# MidiInterface.net
KiCad netlist of a schematic drawn in EAGLE
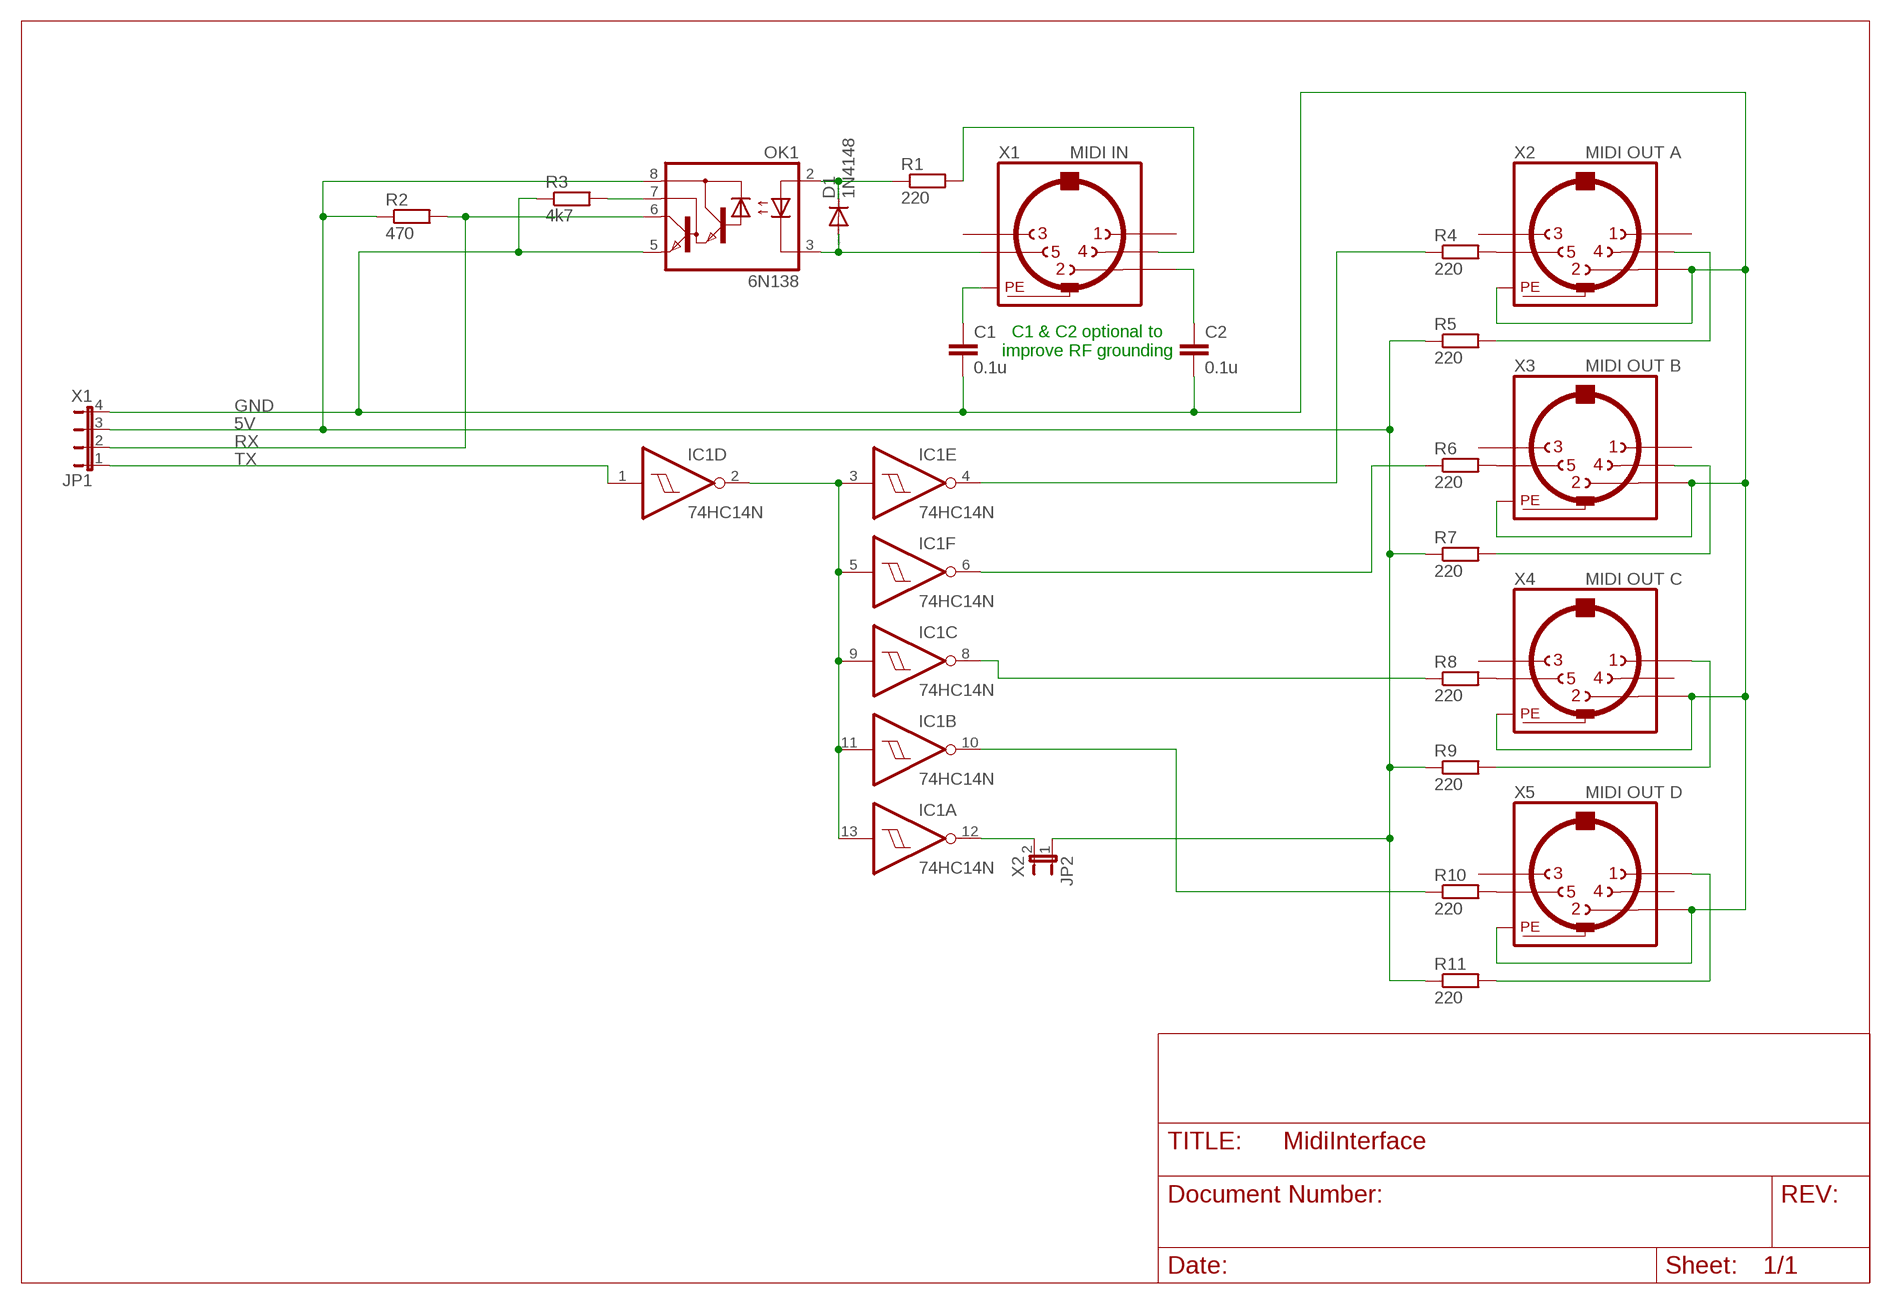
[diagram p0: schematic, sheet 1]

(export (version "E")
  (design (tool "Eeschema 10.0.6"))
  (components
    (comp (ref "C1")
      (value "0.1u")
      (footprint "eagle-import:C025-025X050")
      (libsource (lib "eagle-import") (part "C-EU025-025X050"))
    )
    (comp (ref "C2")
      (value "0.1u")
      (footprint "eagle-import:C025-025X050")
      (libsource (lib "eagle-import") (part "C-EU025-025X050"))
    )
    (comp (ref "D1")
      (value "1N4148")
      (footprint "eagle-import:DO35-7")
      (libsource (lib "eagle-import") (part "1N4148DO35-7"))
    )
    (comp (ref "IC1")
      (value "74HC14N")
      (footprint "eagle-import:DIL14")
      (libsource (lib "eagle-import") (part "7414NHC"))
    )
    (comp (ref "JP1")
      (value "X1")
      (footprint "eagle-import:JP4")
      (libsource (lib "eagle-import") (part "JP4E"))
    )
    (comp (ref "JP2")
      (value "X2")
      (footprint "eagle-import:JP1")
      (libsource (lib "eagle-import") (part "JP1E"))
    )
    (comp (ref "OK1")
      (value "6N138")
      (footprint "eagle-import:DIL08")
      (fields (field (name "MF") "VISHAY/TELEFUNKEN"))
      (libsource (lib "eagle-import") (part "6N138"))
    )
    (comp (ref "R1")
      (value "220")
      (footprint "eagle-import:0204_7")
      (libsource (lib "eagle-import") (part "R-EU_0204/7"))
    )
    (comp (ref "R2")
      (value "470")
      (footprint "eagle-import:0204_7")
      (libsource (lib "eagle-import") (part "R-EU_0204/7"))
    )
    (comp (ref "R3")
      (value "4k7")
      (footprint "eagle-import:0204_7")
      (libsource (lib "eagle-import") (part "R-EU_0204/7"))
    )
    (comp (ref "R4")
      (value "220")
      (footprint "eagle-import:0204_7")
      (libsource (lib "eagle-import") (part "R-EU_0204/7"))
    )
    (comp (ref "R5")
      (value "220")
      (footprint "eagle-import:0204_7")
      (libsource (lib "eagle-import") (part "R-EU_0204/7"))
    )
    (comp (ref "R6")
      (value "220")
      (footprint "eagle-import:0204_7")
      (libsource (lib "eagle-import") (part "R-EU_0204/7"))
    )
    (comp (ref "R7")
      (value "220")
      (footprint "eagle-import:0204_7")
      (libsource (lib "eagle-import") (part "R-EU_0204/7"))
    )
    (comp (ref "R8")
      (value "220")
      (footprint "eagle-import:0204_7")
      (libsource (lib "eagle-import") (part "R-EU_0204/7"))
    )
    (comp (ref "R9")
      (value "220")
      (footprint "eagle-import:0204_7")
      (libsource (lib "eagle-import") (part "R-EU_0204/7"))
    )
    (comp (ref "R10")
      (value "220")
      (footprint "eagle-import:0204_7")
      (libsource (lib "eagle-import") (part "R-EU_0204/7"))
    )
    (comp (ref "R11")
      (value "220")
      (footprint "eagle-import:0204_7")
      (libsource (lib "eagle-import") (part "R-EU_0204/7"))
    )
    (comp (ref "X1")
      (value "MIDI IN")
      (footprint "eagle-import:MAB5SH")
      (libsource (lib "eagle-import") (part "MAB5SH"))
    )
    (comp (ref "X2")
      (value "MIDI OUT A")
      (footprint "eagle-import:MAB5SH")
      (libsource (lib "eagle-import") (part "MAB5SH"))
    )
    (comp (ref "X3")
      (value "MIDI OUT B")
      (footprint "eagle-import:MAB5SH")
      (libsource (lib "eagle-import") (part "MAB5SH"))
    )
    (comp (ref "X4")
      (value "MIDI OUT C")
      (footprint "eagle-import:MAB5SH")
      (libsource (lib "eagle-import") (part "MAB5SH"))
    )
    (comp (ref "X5")
      (value "MIDI OUT D")
      (footprint "eagle-import:MAB5SH")
      (libsource (lib "eagle-import") (part "MAB5SH"))
    )
  )
  (nets
    (net (code "1") (name "/5V") (class "Default")
      (node (ref "JP1") (pin "3") (pinfunction "3_3") (pintype "passive"))
      (node (ref "JP2") (pin "1") (pinfunction "1_1") (pintype "passive"))
      (node (ref "OK1") (pin "8") (pinfunction "VCC_8") (pintype "passive"))
      (node (ref "R11") (pin "1") (pinfunction "1_1") (pintype "passive"))
      (node (ref "R2") (pin "1") (pinfunction "1_1") (pintype "passive"))
      (node (ref "R5") (pin "1") (pinfunction "1_1") (pintype "passive"))
      (node (ref "R7") (pin "1") (pinfunction "1_1") (pintype "passive"))
      (node (ref "R9") (pin "1") (pinfunction "1_1") (pintype "passive"))
    )
    (net (code "2") (name "/GND") (class "Default")
      (node (ref "C1") (pin "2") (pinfunction "2_2") (pintype "passive"))
      (node (ref "C2") (pin "2") (pinfunction "2_2") (pintype "passive"))
      (node (ref "JP1") (pin "4") (pinfunction "4_4") (pintype "passive"))
      (node (ref "OK1") (pin "5") (pinfunction "GND_5") (pintype "passive"))
      (node (ref "R3") (pin "1") (pinfunction "1_1") (pintype "passive"))
      (node (ref "X2") (pin "2") (pinfunction "2_2") (pintype "passive"))
      (node (ref "X2") (pin "PE") (pinfunction "PE_PE") (pintype "power_in"))
      (node (ref "X2") (pin "PE@") (pinfunction "PE_PE@") (pintype "power_in"))
      (node (ref "X3") (pin "2") (pinfunction "2_2") (pintype "passive"))
      (node (ref "X3") (pin "PE") (pinfunction "PE_PE") (pintype "power_in"))
      (node (ref "X3") (pin "PE@") (pinfunction "PE_PE@") (pintype "power_in"))
      (node (ref "X4") (pin "2") (pinfunction "2_2") (pintype "passive"))
      (node (ref "X4") (pin "PE") (pinfunction "PE_PE") (pintype "power_in"))
      (node (ref "X4") (pin "PE@") (pinfunction "PE_PE@") (pintype "power_in"))
      (node (ref "X5") (pin "2") (pinfunction "2_2") (pintype "passive"))
      (node (ref "X5") (pin "PE") (pinfunction "PE_PE") (pintype "power_in"))
      (node (ref "X5") (pin "PE@") (pinfunction "PE_PE@") (pintype "power_in"))
    )
    (net (code "3") (name "/RX") (class "Default")
      (node (ref "JP1") (pin "2") (pinfunction "2_2") (pintype "passive"))
      (node (ref "OK1") (pin "6") (pinfunction "VO_6") (pintype "passive"))
      (node (ref "R2") (pin "2") (pinfunction "2_2") (pintype "passive"))
    )
    (net (code "4") (name "/TX") (class "Default")
      (node (ref "IC1") (pin "1") (pinfunction "I_1") (pintype "input"))
      (node (ref "JP1") (pin "1") (pinfunction "1_1") (pintype "passive"))
    )
    (net (code "5") (name "Net-(C1-Pad1)") (class "Default")
      (node (ref "C1") (pin "1") (pinfunction "1_1") (pintype "passive"))
      (node (ref "X1") (pin "PE") (pinfunction "PE_PE") (pintype "power_in"))
      (node (ref "X1") (pin "PE@") (pinfunction "PE_PE@") (pintype "power_in"))
    )
    (net (code "6") (name "Net-(C2-Pad1)") (class "Default")
      (node (ref "C2") (pin "1") (pinfunction "1_1") (pintype "passive"))
      (node (ref "X1") (pin "2") (pinfunction "2_2") (pintype "passive"))
    )
    (net (code "7") (name "Net-(IC1A-I)") (class "Default")
      (node (ref "IC1") (pin "11") (pinfunction "I_11") (pintype "input"))
      (node (ref "IC1") (pin "13") (pinfunction "I_13") (pintype "input"))
      (node (ref "IC1") (pin "2") (pinfunction "O_2") (pintype "output"))
      (node (ref "IC1") (pin "3") (pinfunction "I_3") (pintype "input"))
      (node (ref "IC1") (pin "5") (pinfunction "I_5") (pintype "input"))
      (node (ref "IC1") (pin "9") (pinfunction "I_9") (pintype "input"))
    )
    (net (code "8") (name "Net-(IC1A-O)") (class "Default")
      (node (ref "IC1") (pin "12") (pinfunction "O_12") (pintype "output"))
      (node (ref "JP2") (pin "2") (pinfunction "2_2") (pintype "passive"))
    )
    (net (code "9") (name "Net-(IC1B-O)") (class "Default")
      (node (ref "IC1") (pin "10") (pinfunction "O_10") (pintype "output"))
      (node (ref "R10") (pin "1") (pinfunction "1_1") (pintype "passive"))
    )
    (net (code "10") (name "Net-(IC1C-O)") (class "Default")
      (node (ref "IC1") (pin "8") (pinfunction "O_8") (pintype "output"))
      (node (ref "R8") (pin "1") (pinfunction "1_1") (pintype "passive"))
    )
    (net (code "11") (name "Net-(IC1E-O)") (class "Default")
      (node (ref "IC1") (pin "4") (pinfunction "O_4") (pintype "output"))
      (node (ref "R4") (pin "1") (pinfunction "1_1") (pintype "passive"))
    )
    (net (code "12") (name "Net-(IC1F-O)") (class "Default")
      (node (ref "IC1") (pin "6") (pinfunction "O_6") (pintype "output"))
      (node (ref "R6") (pin "1") (pinfunction "1_1") (pintype "passive"))
    )
    (net (code "13") (name "Net-(OK1-A)") (class "Default")
      (node (ref "D1") (pin "C") (pinfunction "C_C") (pintype "passive"))
      (node (ref "OK1") (pin "2") (pinfunction "A_2") (pintype "passive"))
      (node (ref "R1") (pin "1") (pinfunction "1_1") (pintype "passive"))
    )
    (net (code "14") (name "Net-(OK1-C)") (class "Default")
      (node (ref "D1") (pin "A") (pinfunction "A_A") (pintype "passive"))
      (node (ref "OK1") (pin "3") (pinfunction "C_3") (pintype "passive"))
      (node (ref "X1") (pin "5") (pinfunction "5_5") (pintype "passive"))
    )
    (net (code "15") (name "Net-(OK1-VB)") (class "Default")
      (node (ref "OK1") (pin "7") (pinfunction "VB_7") (pintype "passive"))
      (node (ref "R3") (pin "2") (pinfunction "2_2") (pintype "passive"))
    )
    (net (code "16") (name "Net-(R1-Pad2)") (class "Default")
      (node (ref "R1") (pin "2") (pinfunction "2_2") (pintype "passive"))
      (node (ref "X1") (pin "4") (pinfunction "4_4") (pintype "passive"))
    )
    (net (code "17") (name "Net-(R4-Pad2)") (class "Default")
      (node (ref "R4") (pin "2") (pinfunction "2_2") (pintype "passive"))
      (node (ref "X2") (pin "5") (pinfunction "5_5") (pintype "passive"))
    )
    (net (code "18") (name "Net-(R5-Pad2)") (class "Default")
      (node (ref "R5") (pin "2") (pinfunction "2_2") (pintype "passive"))
      (node (ref "X2") (pin "4") (pinfunction "4_4") (pintype "passive"))
    )
    (net (code "19") (name "Net-(R6-Pad2)") (class "Default")
      (node (ref "R6") (pin "2") (pinfunction "2_2") (pintype "passive"))
      (node (ref "X3") (pin "5") (pinfunction "5_5") (pintype "passive"))
    )
    (net (code "20") (name "Net-(R7-Pad2)") (class "Default")
      (node (ref "R7") (pin "2") (pinfunction "2_2") (pintype "passive"))
      (node (ref "X3") (pin "4") (pinfunction "4_4") (pintype "passive"))
    )
    (net (code "21") (name "Net-(R8-Pad2)") (class "Default")
      (node (ref "R8") (pin "2") (pinfunction "2_2") (pintype "passive"))
      (node (ref "X4") (pin "5") (pinfunction "5_5") (pintype "passive"))
    )
    (net (code "22") (name "Net-(R9-Pad2)") (class "Default")
      (node (ref "R9") (pin "2") (pinfunction "2_2") (pintype "passive"))
      (node (ref "X4") (pin "1") (pinfunction "1_1") (pintype "passive"))
    )
    (net (code "23") (name "Net-(R10-Pad2)") (class "Default")
      (node (ref "R10") (pin "2") (pinfunction "2_2") (pintype "passive"))
      (node (ref "X5") (pin "5") (pinfunction "5_5") (pintype "passive"))
    )
    (net (code "24") (name "Net-(R11-Pad2)") (class "Default")
      (node (ref "R11") (pin "2") (pinfunction "2_2") (pintype "passive"))
      (node (ref "X5") (pin "1") (pinfunction "1_1") (pintype "passive"))
    )
    (net (code "25") (name "unconnected-(X1-Pad1)") (class "Default")
      (node (ref "X1") (pin "1") (pinfunction "1_1") (pintype "passive"))
    )
    (net (code "26") (name "unconnected-(X1-Pad3)") (class "Default")
      (node (ref "X1") (pin "3") (pinfunction "3_3") (pintype "passive"))
    )
    (net (code "27") (name "unconnected-(X2-Pad1)") (class "Default")
      (node (ref "X2") (pin "1") (pinfunction "1_1") (pintype "passive"))
    )
    (net (code "28") (name "unconnected-(X2-Pad3)") (class "Default")
      (node (ref "X2") (pin "3") (pinfunction "3_3") (pintype "passive"))
    )
    (net (code "29") (name "unconnected-(X3-Pad1)") (class "Default")
      (node (ref "X3") (pin "1") (pinfunction "1_1") (pintype "passive"))
    )
    (net (code "30") (name "unconnected-(X3-Pad3)") (class "Default")
      (node (ref "X3") (pin "3") (pinfunction "3_3") (pintype "passive"))
    )
    (net (code "31") (name "unconnected-(X4-Pad3)") (class "Default")
      (node (ref "X4") (pin "3") (pinfunction "3_3") (pintype "passive"))
    )
    (net (code "32") (name "unconnected-(X4-Pad4)") (class "Default")
      (node (ref "X4") (pin "4") (pinfunction "4_4") (pintype "passive"))
    )
    (net (code "33") (name "unconnected-(X5-Pad3)") (class "Default")
      (node (ref "X5") (pin "3") (pinfunction "3_3") (pintype "passive"))
    )
    (net (code "34") (name "unconnected-(X5-Pad4)") (class "Default")
      (node (ref "X5") (pin "4") (pinfunction "4_4") (pintype "passive"))
    )
  )
)
